# LOCAL_POWER.net
KiCad netlist of a schematic drawn in Altium Designer
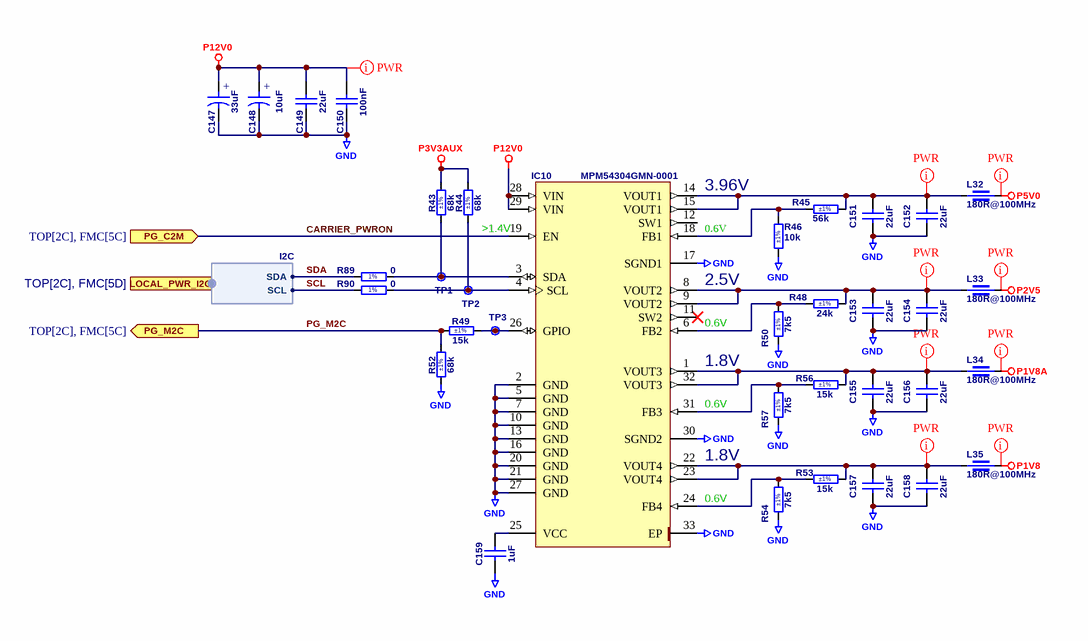
[diagram p0: LOCAL_POWER.SchDoc]

(export (version "E")
  (design (tool "Eeschema 10.0.6"))
  (components
    (comp (ref "C147")
      (value "33uF")
      (footprint "CAPMP3528X210N")
      (description "Polarised capacitor")
      (fields
        (field (name "PART NUMBER") "CTE3528-21_33UF_16V_10%")
        (field (name "VOLTAGE") "16V")
        (field (name "AUTHOR") "CERN DEM JLC")
      )
      (libsource (lib "Capacitors") (part "Capacitor - polarized"))
    )
    (comp (ref "C148")
      (value "10uF")
      (footprint "CAPMP3216X180N")
      (description "Polarised capacitor")
      (fields
        (field (name "PART NUMBER") "CTE3216-18_10UF_16V_20%_AVX_TCJ")
        (field (name "VOLTAGE") "16V")
        (field (name "AUTHOR") "CERN DEM JLC")
      )
      (libsource (lib "Capacitors") (part "Capacitor - polarized"))
    )
    (comp (ref "C149")
      (value "22uF")
      (footprint "CAPC2012X135N")
      (description "Non-polarised capacitor")
      (fields
        (field (name "MANUFACTURER PART NUMBER") "CC0805_22UF_16V_10%_X5R")
        (field (name "MANUFACTURER") "GENERIC")
        (field (name "AUTHOR") "CERN DEM JLC")
      )
      (libsource (lib "Capacitors") (part "Capacitor - non polarized"))
    )
    (comp (ref "C150")
      (value "100nF")
      (footprint "CAPC1005X55N")
      (description "Non-polarised capacitor")
      (fields
        (field (name "PART NUMBER") "CC0402_100NF_16V_10%_X7R")
        (field (name "VOLTAGE") "16V")
        (field (name "AUTHOR") "CERN DEM JLC")
      )
      (libsource (lib "Capacitors") (part "Capacitor - non polarized"))
    )
    (comp (ref "C151")
      (value "22uF")
      (footprint "CAPC2012X135N")
      (description "Non-polarised capacitor")
      (fields
        (field (name "MANUFACTURER PART NUMBER") "CC0805_22UF_16V_10%_X5R")
        (field (name "MANUFACTURER") "GENERIC")
        (field (name "AUTHOR") "CERN DEM JLC")
      )
      (libsource (lib "Capacitors") (part "Capacitor - non polarized"))
    )
    (comp (ref "C152")
      (value "22uF")
      (footprint "CAPC2012X135N")
      (description "Non-polarised capacitor")
      (fields
        (field (name "MANUFACTURER PART NUMBER") "CC0805_22UF_16V_10%_X5R")
        (field (name "MANUFACTURER") "GENERIC")
        (field (name "AUTHOR") "CERN DEM JLC")
      )
      (libsource (lib "Capacitors") (part "Capacitor - non polarized"))
    )
    (comp (ref "C153")
      (value "22uF")
      (footprint "CAPC2012X135N")
      (description "Non-polarised capacitor")
      (fields
        (field (name "MANUFACTURER PART NUMBER") "CC0805_22UF_16V_10%_X5R")
        (field (name "MANUFACTURER") "GENERIC")
        (field (name "AUTHOR") "CERN DEM JLC")
      )
      (libsource (lib "Capacitors") (part "Capacitor - non polarized"))
    )
    (comp (ref "C154")
      (value "22uF")
      (footprint "CAPC2012X135N")
      (description "Non-polarised capacitor")
      (fields
        (field (name "MANUFACTURER PART NUMBER") "CC0805_22UF_16V_10%_X5R")
        (field (name "MANUFACTURER") "GENERIC")
        (field (name "AUTHOR") "CERN DEM JLC")
      )
      (libsource (lib "Capacitors") (part "Capacitor - non polarized"))
    )
    (comp (ref "C155")
      (value "22uF")
      (footprint "CAPC2012X135N")
      (description "Non-polarised capacitor")
      (fields
        (field (name "MANUFACTURER PART NUMBER") "CC0805_22UF_16V_10%_X5R")
        (field (name "MANUFACTURER") "GENERIC")
        (field (name "AUTHOR") "CERN DEM JLC")
      )
      (libsource (lib "Capacitors") (part "Capacitor - non polarized"))
    )
    (comp (ref "C156")
      (value "22uF")
      (footprint "CAPC2012X135N")
      (description "Non-polarised capacitor")
      (fields
        (field (name "MANUFACTURER PART NUMBER") "CC0805_22UF_16V_10%_X5R")
        (field (name "MANUFACTURER") "GENERIC")
        (field (name "AUTHOR") "CERN DEM JLC")
      )
      (libsource (lib "Capacitors") (part "Capacitor - non polarized"))
    )
    (comp (ref "C157")
      (value "22uF")
      (footprint "CAPC2012X135N")
      (description "Non-polarised capacitor")
      (fields
        (field (name "MANUFACTURER PART NUMBER") "CC0805_22UF_16V_10%_X5R")
        (field (name "MANUFACTURER") "GENERIC")
        (field (name "AUTHOR") "CERN DEM JLC")
      )
      (libsource (lib "Capacitors") (part "Capacitor - non polarized"))
    )
    (comp (ref "C158")
      (value "22uF")
      (footprint "CAPC2012X135N")
      (description "Non-polarised capacitor")
      (fields
        (field (name "MANUFACTURER PART NUMBER") "CC0805_22UF_16V_10%_X5R")
        (field (name "MANUFACTURER") "GENERIC")
        (field (name "AUTHOR") "CERN DEM JLC")
      )
      (libsource (lib "Capacitors") (part "Capacitor - non polarized"))
    )
    (comp (ref "C159")
      (value "1uF")
      (footprint "CAPC1005X55N")
      (description "Non-polarised capacitor")
      (fields
        (field (name "PART NUMBER") "CC0402_1UF_16V_10%_X5R")
        (field (name "VOLTAGE") "16V")
        (field (name "AUTHOR") "CERN DEM JLC")
      )
      (libsource (lib "Capacitors") (part "Capacitor - non polarized"))
    )
    (comp (ref "IC10")
      (value "MPM54304GMN-0001")
      (footprint "MPS_MPM54304GMN")
      (description "Quad-Output Power Module with I2C and MTP")
      (fields
        (field (name "MANUFACTURER") "MPS (MONOLITIC  POWER SYSTEMS)")
        (field (name "MANUFACTURER PART NUMBER") "MPM54304GMN-002")
        (field (name "AUTHOR") "CERN DEM BC")
      )
      (libsource (lib "ICs And Semiconductors") (part "MPM54304GMN"))
    )
    (comp (ref "L32")
      (value "180R@100MHz")
      (footprint "INDC2012X105N")
      (fields
        (field (name "PART NUMBER") "IND0805_MURATA_BLM21SP181BH1D")
        (field (name "POWER") "4A")
        (field (name "TOLERANCE") "±25%")
        (field (name "AUTHOR") "CERN DEM JMW")
      )
      (libsource (lib "Inductors & Transformers") (part "Ferrite Bead"))
    )
    (comp (ref "L33")
      (value "180R@100MHz")
      (footprint "INDC2012X105N")
      (fields
        (field (name "PART NUMBER") "IND0805_MURATA_BLM21SP181BH1D")
        (field (name "POWER") "4A")
        (field (name "TOLERANCE") "±25%")
        (field (name "AUTHOR") "CERN DEM JMW")
      )
      (libsource (lib "Inductors & Transformers") (part "Ferrite Bead"))
    )
    (comp (ref "L34")
      (value "180R@100MHz")
      (footprint "INDC2012X105N")
      (fields
        (field (name "PART NUMBER") "IND0805_MURATA_BLM21SP181BH1D")
        (field (name "POWER") "4A")
        (field (name "TOLERANCE") "±25%")
        (field (name "AUTHOR") "CERN DEM JMW")
      )
      (libsource (lib "Inductors & Transformers") (part "Ferrite Bead"))
    )
    (comp (ref "L35")
      (value "180R@100MHz")
      (footprint "INDC2012X105N")
      (fields
        (field (name "PART NUMBER") "IND0805_MURATA_BLM21SP181BH1D")
        (field (name "POWER") "4A")
        (field (name "TOLERANCE") "±25%")
        (field (name "AUTHOR") "CERN DEM JMW")
      )
      (libsource (lib "Inductors & Transformers") (part "Ferrite Bead"))
    )
    (comp (ref "R43")
      (value "68k")
      (footprint "RESC1005X40N")
      (description "Resistor - 1%")
      (fields
        (field (name "TOLERANCE") "±1%")
        (field (name "PART NUMBER") "R0402_68K_1%_0.0625W_100PPM")
        (field (name "POWER") "0.0625W")
        (field (name "AUTHOR") "CERN DEM JLC")
      )
      (libsource (lib "Resistors") (part "Resistor - 1%"))
    )
    (comp (ref "R44")
      (value "68k")
      (footprint "RESC1005X40N")
      (description "Resistor - 1%")
      (fields
        (field (name "TOLERANCE") "±1%")
        (field (name "PART NUMBER") "R0402_68K_1%_0.0625W_100PPM")
        (field (name "POWER") "0.0625W")
        (field (name "AUTHOR") "CERN DEM JLC")
      )
      (libsource (lib "Resistors") (part "Resistor - 1%"))
    )
    (comp (ref "R45")
      (value "56k")
      (footprint "RESC1005X40N")
      (description "Resistor - 1%")
      (fields
        (field (name "TOLERANCE") "±1%")
        (field (name "PART NUMBER") "R0402_56K_1%_0.0625W_100PPM")
        (field (name "POWER") "0.0625W")
        (field (name "AUTHOR") "CERN DEM JLC")
      )
      (libsource (lib "Resistors") (part "Resistor - 1%"))
    )
    (comp (ref "R46")
      (value "10k")
      (footprint "RESC1005X40N")
      (description "Resistor - 1%")
      (fields
        (field (name "TOLERANCE") "±1%")
        (field (name "PART NUMBER") "R0402_10K_1%_0.0625W_100PPM")
        (field (name "POWER") "0.0625W")
        (field (name "AUTHOR") "CERN DEM JLC")
      )
      (libsource (lib "Resistors") (part "Resistor - 1%"))
    )
    (comp (ref "R48")
      (value "24k")
      (footprint "RESC1005X40N")
      (description "Resistor - 1%")
      (fields
        (field (name "TOLERANCE") "±1%")
        (field (name "PART NUMBER") "R0402_24K_1%_0.0625W_100PPM")
        (field (name "POWER") "0.0625W")
        (field (name "AUTHOR") "CERN DEM JLC")
      )
      (libsource (lib "Resistors") (part "Resistor - 1%"))
    )
    (comp (ref "R49")
      (value "15k")
      (footprint "RESC1005X40N")
      (description "Resistor - 1%")
      (fields
        (field (name "TOLERANCE") "±1%")
        (field (name "PART NUMBER") "R0402_15K_1%_0.0625W_100PPM")
        (field (name "POWER") "0.0625W")
        (field (name "AUTHOR") "CERN DEM JMW")
      )
      (libsource (lib "Resistors") (part "Resistor - 1%"))
    )
    (comp (ref "R50")
      (value "7k5")
      (footprint "RESC1005X40N")
      (description "Resistor - 1%")
      (fields
        (field (name "TOLERANCE") "±1%")
        (field (name "PART NUMBER") "R0402_7K5_1%_0.0625W_100PPM")
        (field (name "POWER") "0.0625W")
        (field (name "AUTHOR") "CERN DEM JLC")
      )
      (libsource (lib "Resistors") (part "Resistor - 1%"))
    )
    (comp (ref "R52")
      (value "68k")
      (footprint "RESC1005X40N")
      (description "Resistor - 1%")
      (fields
        (field (name "TOLERANCE") "±1%")
        (field (name "PART NUMBER") "R0402_68K_1%_0.0625W_100PPM")
        (field (name "POWER") "0.0625W")
        (field (name "AUTHOR") "CERN DEM JLC")
      )
      (libsource (lib "Resistors") (part "Resistor - 1%"))
    )
    (comp (ref "R53")
      (value "15k")
      (footprint "RESC1005X40N")
      (description "Resistor - 1%")
      (fields
        (field (name "TOLERANCE") "±1%")
        (field (name "PART NUMBER") "R0402_15K_1%_0.0625W_100PPM")
        (field (name "POWER") "0.0625W")
        (field (name "AUTHOR") "CERN DEM JMW")
      )
      (libsource (lib "Resistors") (part "Resistor - 1%"))
    )
    (comp (ref "R54")
      (value "7k5")
      (footprint "RESC1005X40N")
      (description "Resistor - 1%")
      (fields
        (field (name "TOLERANCE") "±1%")
        (field (name "PART NUMBER") "R0402_7K5_1%_0.0625W_100PPM")
        (field (name "POWER") "0.0625W")
        (field (name "AUTHOR") "CERN DEM JLC")
      )
      (libsource (lib "Resistors") (part "Resistor - 1%"))
    )
    (comp (ref "R56")
      (value "15k")
      (footprint "RESC1005X40N")
      (description "Resistor - 1%")
      (fields
        (field (name "TOLERANCE") "±1%")
        (field (name "PART NUMBER") "R0402_15K_1%_0.0625W_100PPM")
        (field (name "POWER") "0.0625W")
        (field (name "AUTHOR") "CERN DEM JMW")
      )
      (libsource (lib "Resistors") (part "Resistor - 1%"))
    )
    (comp (ref "R57")
      (value "7k5")
      (footprint "RESC1005X40N")
      (description "Resistor - 1%")
      (fields
        (field (name "TOLERANCE") "±1%")
        (field (name "PART NUMBER") "R0402_7K5_1%_0.0625W_100PPM")
        (field (name "POWER") "0.0625W")
        (field (name "AUTHOR") "CERN DEM JLC")
      )
      (libsource (lib "Resistors") (part "Resistor - 1%"))
    )
    (comp (ref "R89")
      (value "0")
      (footprint "RESC1005X40N")
      (description "Resistor - 1%")
      (fields
        (field (name "PART NUMBER") "R0402_0R_JUMPER")
        (field (name "MANUFACTURER") "GENERIC")
        (field (name "AUTHOR") "CERN DEM JLC")
      )
      (libsource (lib "Resistors") (part "Resistor - 1%"))
    )
    (comp (ref "R90")
      (value "0")
      (footprint "RESC1005X40N")
      (description "Resistor - 1%")
      (fields
        (field (name "PART NUMBER") "R0402_0R_JUMPER")
        (field (name "MANUFACTURER") "GENERIC")
        (field (name "AUTHOR") "CERN DEM JLC")
      )
      (libsource (lib "Resistors") (part "Resistor - 1%"))
    )
    (comp (ref "TP1")
      (value "Test Point")
      (footprint "TPS127")
      (fields (field (name "PART NUMBER") "SMD_PAD_1.27X1.27MM") (field (name "AUTHOR") "CERN DEM JLC"))
      (libsource (lib "Eletro-mechanical") (part "Test Point"))
    )
    (comp (ref "TP2")
      (value "Test Point")
      (footprint "TPS127")
      (fields (field (name "PART NUMBER") "SMD_PAD_1.27X1.27MM") (field (name "AUTHOR") "CERN DEM JLC"))
      (libsource (lib "Eletro-mechanical") (part "Test Point"))
    )
    (comp (ref "TP3")
      (value "Test Point")
      (footprint "TPS127")
      (fields (field (name "PART NUMBER") "SMD_PAD_1.27X1.27MM") (field (name "AUTHOR") "CERN DEM JLC"))
      (libsource (lib "Eletro-mechanical") (part "Test Point"))
    )
  )
  (nets
    (net (code "2") (name "/CARRIER_PWRON") (class "Default")
      (node (ref "IC10") (pin "19") (pinfunction "EN_19") (pintype "input"))
    )
    (net (code "3") (name "/PG_M2C") (class "Default")
      (node (ref "R49") (pin "1") (pinfunction "1_1") (pintype "passive"))
      (node (ref "R52") (pin "2") (pinfunction "2_2") (pintype "passive"))
    )
    (net (code "4") (name "/SCL") (class "Default")
      (node (ref "R90") (pin "2") (pinfunction "2_2") (pintype "passive"))
    )
    (net (code "5") (name "/SDA") (class "Default")
      (node (ref "R89") (pin "2") (pinfunction "2_2") (pintype "passive"))
    )
    (net (code "7") (name "GND") (class "Default")
      (node (ref "C147") (pin "2") (pinfunction "2_2") (pintype "passive"))
      (node (ref "C148") (pin "2") (pinfunction "2_2") (pintype "passive"))
      (node (ref "C149") (pin "1") (pinfunction "1_1") (pintype "passive"))
      (node (ref "C150") (pin "1") (pinfunction "1_1") (pintype "passive"))
      (node (ref "C151") (pin "1") (pinfunction "1_1") (pintype "passive"))
      (node (ref "C152") (pin "1") (pinfunction "1_1") (pintype "passive"))
      (node (ref "C153") (pin "1") (pinfunction "1_1") (pintype "passive"))
      (node (ref "C154") (pin "1") (pinfunction "1_1") (pintype "passive"))
      (node (ref "C155") (pin "1") (pinfunction "1_1") (pintype "passive"))
      (node (ref "C156") (pin "1") (pinfunction "1_1") (pintype "passive"))
      (node (ref "C157") (pin "1") (pinfunction "1_1") (pintype "passive"))
      (node (ref "C158") (pin "1") (pinfunction "1_1") (pintype "passive"))
      (node (ref "C159") (pin "1") (pinfunction "1_1") (pintype "passive"))
      (node (ref "IC10") (pin "10") (pinfunction "GND_10") (pintype "power_in"))
      (node (ref "IC10") (pin "13") (pinfunction "GND_13") (pintype "power_in"))
      (node (ref "IC10") (pin "16") (pinfunction "GND_16") (pintype "power_in"))
      (node (ref "IC10") (pin "17") (pinfunction "SGND1_17") (pintype "power_in"))
      (node (ref "IC10") (pin "2") (pinfunction "GND_2") (pintype "power_in"))
      (node (ref "IC10") (pin "20") (pinfunction "GND_20") (pintype "power_in"))
      (node (ref "IC10") (pin "21") (pinfunction "GND_21") (pintype "power_in"))
      (node (ref "IC10") (pin "27") (pinfunction "GND_27") (pintype "power_in"))
      (node (ref "IC10") (pin "30") (pinfunction "SGND2_30") (pintype "power_in"))
      (node (ref "IC10") (pin "33") (pinfunction "EP_33") (pintype "power_in"))
      (node (ref "IC10") (pin "5") (pinfunction "GND_5") (pintype "power_in"))
      (node (ref "IC10") (pin "7") (pinfunction "GND_7") (pintype "power_in"))
      (node (ref "R46") (pin "1") (pinfunction "1_1") (pintype "passive"))
      (node (ref "R50") (pin "1") (pinfunction "1_1") (pintype "passive"))
      (node (ref "R52") (pin "1") (pinfunction "1_1") (pintype "passive"))
      (node (ref "R54") (pin "1") (pinfunction "1_1") (pintype "passive"))
      (node (ref "R57") (pin "1") (pinfunction "1_1") (pintype "passive"))
    )
    (net (code "8") (name "Net-(C151-Pad2)") (class "Default")
      (node (ref "C151") (pin "2") (pinfunction "2_2") (pintype "passive"))
      (node (ref "C152") (pin "2") (pinfunction "2_2") (pintype "passive"))
      (node (ref "IC10") (pin "14") (pinfunction "VOUT1_14") (pintype "output"))
      (node (ref "IC10") (pin "15") (pinfunction "VOUT1_15") (pintype "output"))
      (node (ref "L32") (pin "1") (pinfunction "1_1") (pintype "passive"))
      (node (ref "R45") (pin "2") (pinfunction "2_2") (pintype "passive"))
    )
    (net (code "9") (name "Net-(C153-Pad2)") (class "Default")
      (node (ref "C153") (pin "2") (pinfunction "2_2") (pintype "passive"))
      (node (ref "C154") (pin "2") (pinfunction "2_2") (pintype "passive"))
      (node (ref "IC10") (pin "8") (pinfunction "VOUT2_8") (pintype "output"))
      (node (ref "IC10") (pin "9") (pinfunction "VOUT2_9") (pintype "output"))
      (node (ref "L33") (pin "1") (pinfunction "1_1") (pintype "passive"))
      (node (ref "R48") (pin "2") (pinfunction "2_2") (pintype "passive"))
    )
    (net (code "10") (name "Net-(C155-Pad2)") (class "Default")
      (node (ref "C155") (pin "2") (pinfunction "2_2") (pintype "passive"))
      (node (ref "C156") (pin "2") (pinfunction "2_2") (pintype "passive"))
      (node (ref "IC10") (pin "1") (pinfunction "VOUT3_1") (pintype "output"))
      (node (ref "IC10") (pin "32") (pinfunction "VOUT3_32") (pintype "output"))
      (node (ref "L34") (pin "1") (pinfunction "1_1") (pintype "passive"))
      (node (ref "R56") (pin "2") (pinfunction "2_2") (pintype "passive"))
    )
    (net (code "11") (name "Net-(C157-Pad2)") (class "Default")
      (node (ref "C157") (pin "2") (pinfunction "2_2") (pintype "passive"))
      (node (ref "C158") (pin "2") (pinfunction "2_2") (pintype "passive"))
      (node (ref "IC10") (pin "22") (pinfunction "VOUT4_22") (pintype "output"))
      (node (ref "IC10") (pin "23") (pinfunction "VOUT4_23") (pintype "output"))
      (node (ref "L35") (pin "1") (pinfunction "1_1") (pintype "passive"))
      (node (ref "R53") (pin "2") (pinfunction "2_2") (pintype "passive"))
    )
    (net (code "12") (name "Net-(IC10-FB1)") (class "Default")
      (node (ref "IC10") (pin "18") (pinfunction "FB1_18") (pintype "input"))
      (node (ref "R45") (pin "1") (pinfunction "1_1") (pintype "passive"))
      (node (ref "R46") (pin "2") (pinfunction "2_2") (pintype "passive"))
    )
    (net (code "13") (name "Net-(IC10-FB2)") (class "Default")
      (node (ref "IC10") (pin "6") (pinfunction "FB2_6") (pintype "input"))
      (node (ref "R48") (pin "1") (pinfunction "1_1") (pintype "passive"))
      (node (ref "R50") (pin "2") (pinfunction "2_2") (pintype "passive"))
    )
    (net (code "14") (name "Net-(IC10-FB3)") (class "Default")
      (node (ref "IC10") (pin "31") (pinfunction "FB3_31") (pintype "input"))
      (node (ref "R56") (pin "1") (pinfunction "1_1") (pintype "passive"))
      (node (ref "R57") (pin "2") (pinfunction "2_2") (pintype "passive"))
    )
    (net (code "15") (name "Net-(IC10-FB4)") (class "Default")
      (node (ref "IC10") (pin "24") (pinfunction "FB4_24") (pintype "input"))
      (node (ref "R53") (pin "1") (pinfunction "1_1") (pintype "passive"))
      (node (ref "R54") (pin "2") (pinfunction "2_2") (pintype "passive"))
    )
    (net (code "16") (name "Net-(IC10-GPIO)") (class "Default")
      (node (ref "IC10") (pin "26") (pinfunction "GPIO_26") (pintype "bidirectional"))
      (node (ref "R49") (pin "2") (pinfunction "2_2") (pintype "passive"))
      (node (ref "TP3") (pin "1") (pinfunction "1_1") (pintype "bidirectional"))
    )
    (net (code "17") (name "Net-(IC10-SCL)") (class "Default")
      (node (ref "IC10") (pin "4") (pinfunction "SCL_4") (pintype "input"))
      (node (ref "R44") (pin "1") (pinfunction "1_1") (pintype "passive"))
      (node (ref "R90") (pin "1") (pinfunction "1_1") (pintype "passive"))
      (node (ref "TP2") (pin "1") (pinfunction "1_1") (pintype "bidirectional"))
    )
    (net (code "18") (name "Net-(IC10-SDA)") (class "Default")
      (node (ref "IC10") (pin "3") (pinfunction "SDA_3") (pintype "bidirectional"))
      (node (ref "R43") (pin "1") (pinfunction "1_1") (pintype "passive"))
      (node (ref "R89") (pin "1") (pinfunction "1_1") (pintype "passive"))
      (node (ref "TP1") (pin "1") (pinfunction "1_1") (pintype "bidirectional"))
    )
    (net (code "19") (name "Net-(IC10-VCC)") (class "Default")
      (node (ref "C159") (pin "2") (pinfunction "2_2") (pintype "passive"))
      (node (ref "IC10") (pin "25") (pinfunction "VCC_25") (pintype "power_in"))
    )
    (net (code "20") (name "P1V8") (class "Default")
      (node (ref "L35") (pin "2") (pinfunction "2_2") (pintype "passive"))
    )
    (net (code "21") (name "P1V8A") (class "Default")
      (node (ref "L34") (pin "2") (pinfunction "2_2") (pintype "passive"))
    )
    (net (code "22") (name "P2V5") (class "Default")
      (node (ref "L33") (pin "2") (pinfunction "2_2") (pintype "passive"))
    )
    (net (code "23") (name "P3V3AUX") (class "Default")
      (node (ref "R43") (pin "2") (pinfunction "2_2") (pintype "passive"))
      (node (ref "R44") (pin "2") (pinfunction "2_2") (pintype "passive"))
    )
    (net (code "24") (name "P5V0") (class "Default")
      (node (ref "L32") (pin "2") (pinfunction "2_2") (pintype "passive"))
    )
    (net (code "25") (name "P12V0") (class "Default")
      (node (ref "C147") (pin "1") (pinfunction "1_1") (pintype "passive"))
      (node (ref "C148") (pin "1") (pinfunction "1_1") (pintype "passive"))
      (node (ref "C149") (pin "2") (pinfunction "2_2") (pintype "passive"))
      (node (ref "C150") (pin "2") (pinfunction "2_2") (pintype "passive"))
      (node (ref "IC10") (pin "28") (pinfunction "VIN_28") (pintype "input"))
      (node (ref "IC10") (pin "29") (pinfunction "VIN_29") (pintype "input"))
    )
    (net (code "26") (name "unconnected-(IC10-SW1-Pad12)") (class "Default")
      (node (ref "IC10") (pin "12") (pinfunction "SW1_12") (pintype "output"))
    )
    (net (code "27") (name "unconnected-(IC10-SW2-Pad11)") (class "Default")
      (node (ref "IC10") (pin "11") (pinfunction "SW2_11") (pintype "output+no_connect"))
    )
  )
)
